# LM-008.net
KiCad netlist of a schematic drawn in Altium Designer
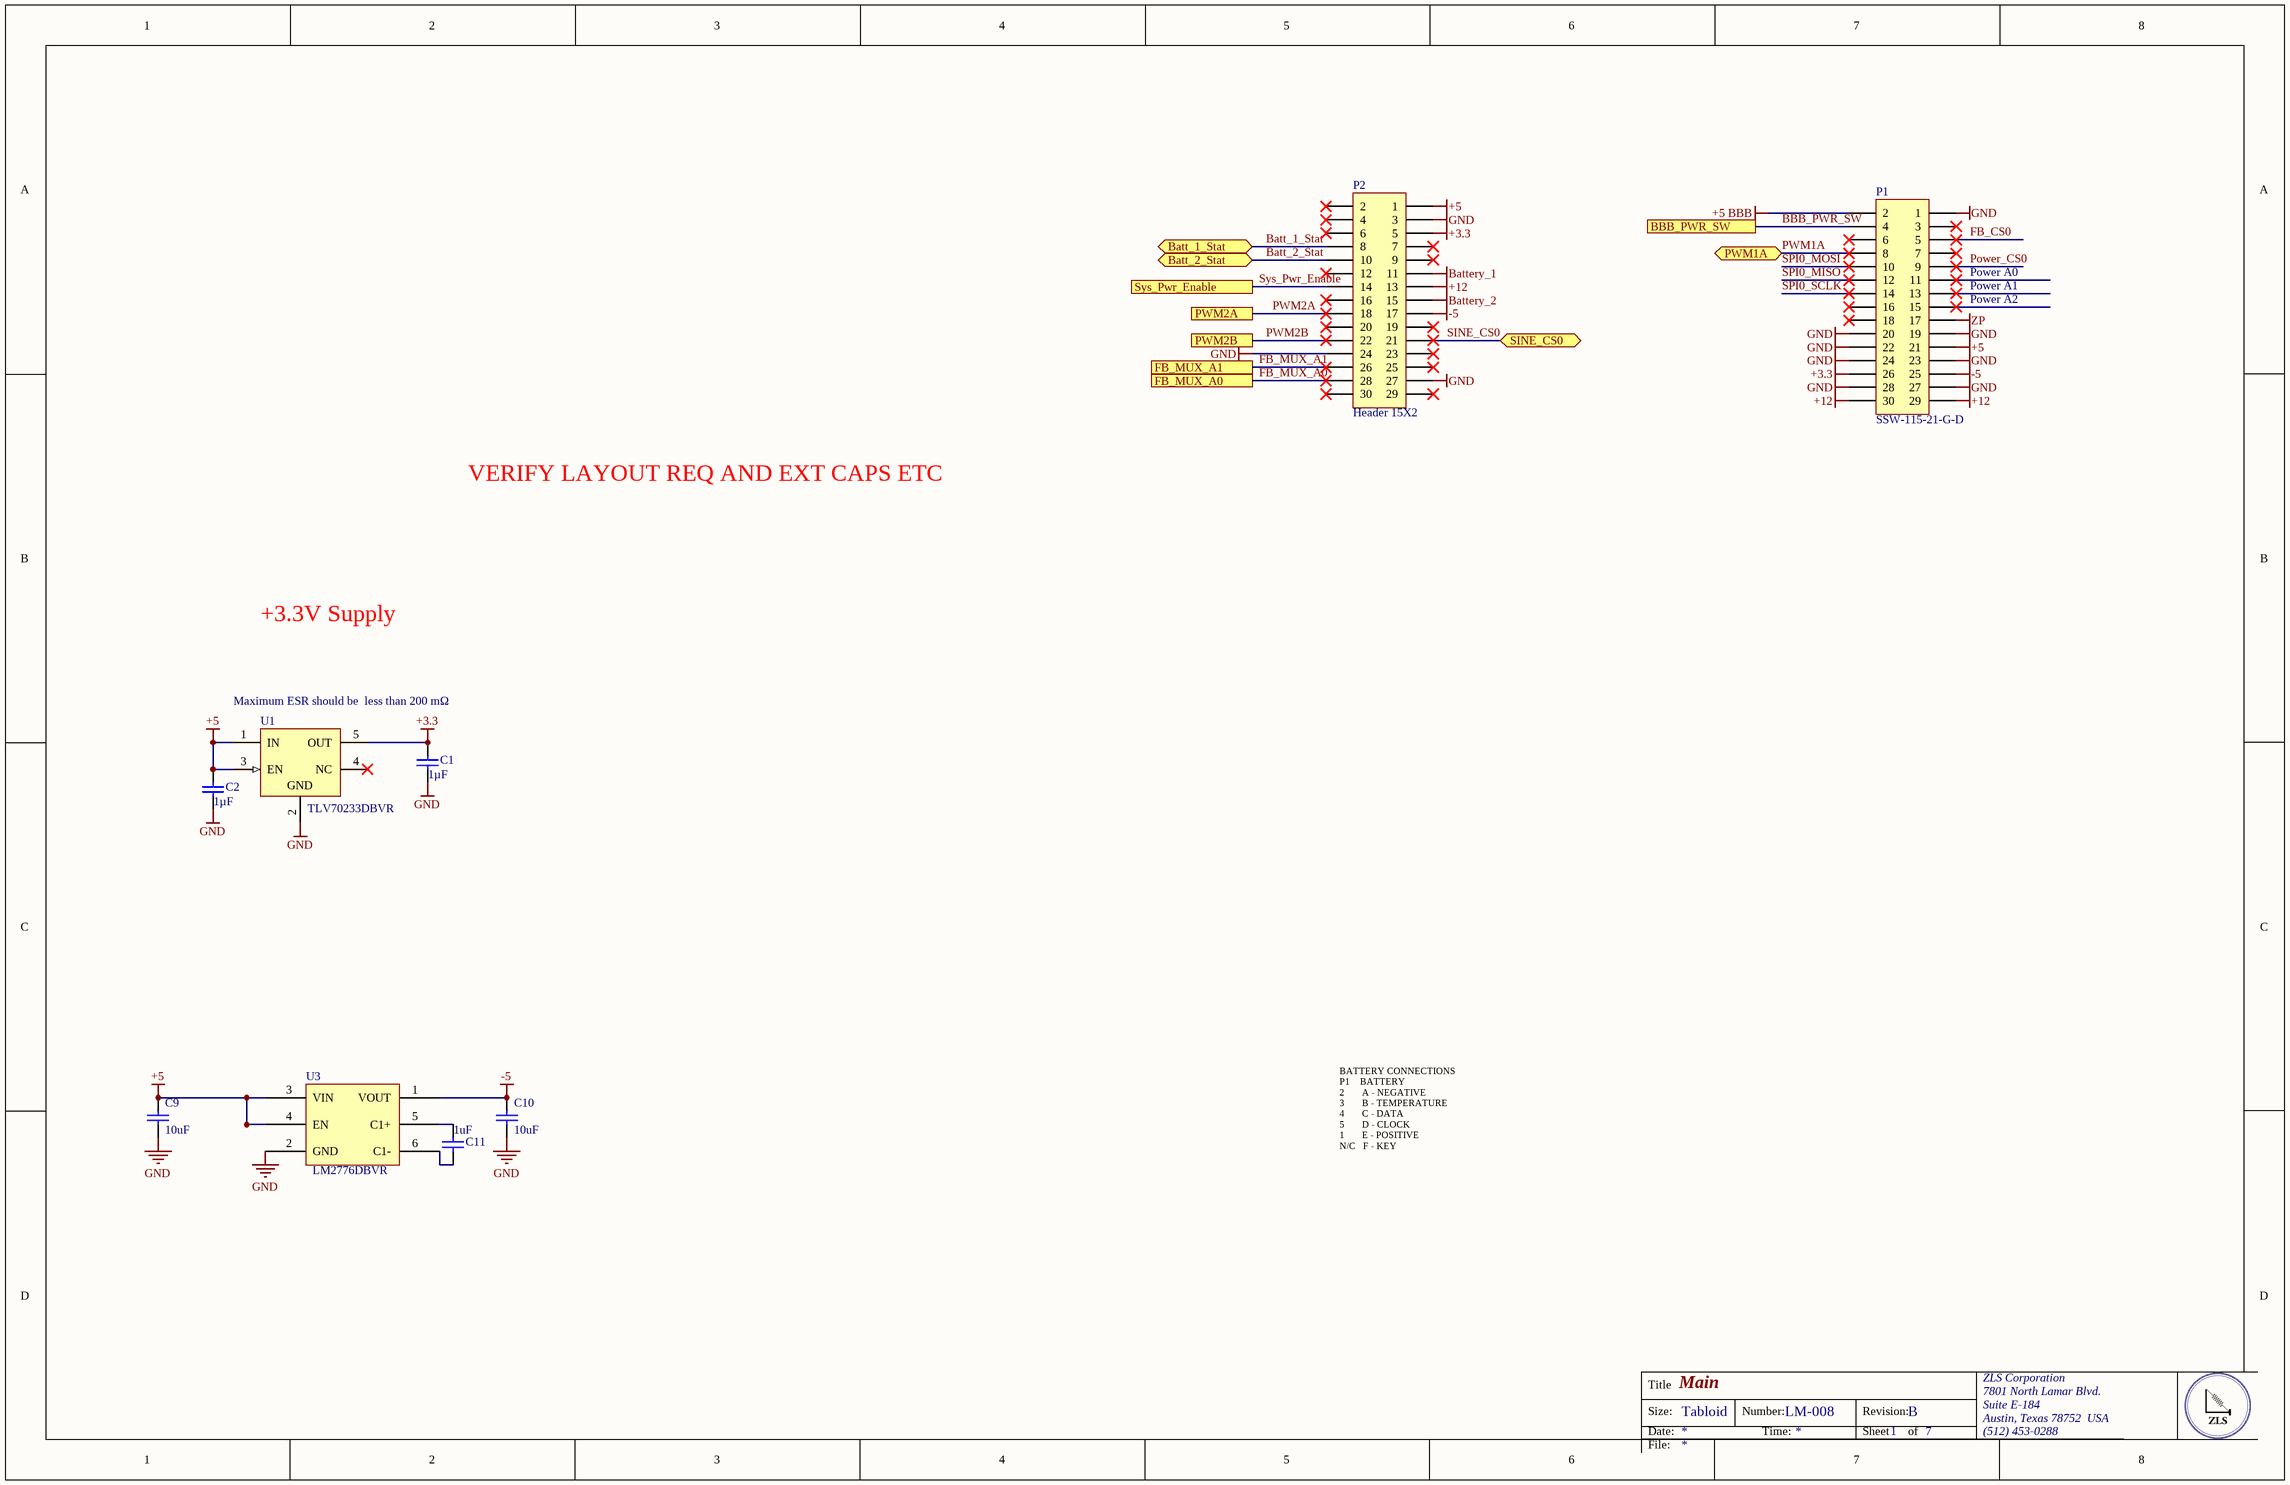
[diagram p0: LM-008.SchDoc]

(export (version "E")
  (design (tool "Eeschema 10.0.6"))
  (components
    (comp (ref "C1")
      (value "CAP CER 1UF 50V X7R 1210")
      (footprint "CAPC1206(3216)130_N")
      (fields
        (field (name "MANUFACTURER") "Murata Electronics North America")
        (field (name "MANUFACTURER PART NUMBER") "GRM32RR71H105KA01L")
        (field (name "CAPACITANCE") "1µF")
        (field (name "TOLERANCE") "±10%")
      )
      (libsource (lib "Altium Content Vault") (part "CMP-1037-04913-1"))
    )
    (comp (ref "C2")
      (value "CAP CER 1UF 50V X7R 1210")
      (footprint "CAPC1206(3216)130_N")
      (fields
        (field (name "MANUFACTURER") "Murata Electronics North America")
        (field (name "MANUFACTURER PART NUMBER") "GRM32RR71H105KA01L")
        (field (name "CAPACITANCE") "1µF")
        (field (name "TOLERANCE") "±10%")
      )
      (libsource (lib "Altium Content Vault") (part "CMP-1037-04913-1"))
    )
    (comp (ref "C9")
      (value "10uF")
      (footprint "CAPC0805(2012)145_N")
      (description "CAP CER 10UF 16V X6S 0805")
      (fields
        (field (name "MANUFACTURER") "TDK Corporation")
        (field (name "MANUFACTURER PART NUMBER") "C2012X6S1C106K085AC")
      )
      (libsource (lib "Altium Content Vault") (part "CMP-1036-04795-1"))
    )
    (comp (ref "C10")
      (value "10uF")
      (footprint "CAPC0805(2012)145_N")
      (description "CAP CER 10UF 16V X6S 0805")
      (fields
        (field (name "MANUFACTURER") "TDK Corporation")
        (field (name "MANUFACTURER PART NUMBER") "C2012X6S1C106K085AC")
      )
      (libsource (lib "Altium Content Vault") (part "CMP-1036-04795-1"))
    )
    (comp (ref "C11")
      (value "1uF")
      (footprint "CAPC0805(2012)145_N")
      (description "CAP CER 1UF 25V X7R 0805")
      (fields
        (field (name "MANUFACTURER") "Yageo")
        (field (name "MANUFACTURER PART NUMBER") "CC0805KKX7R6BB105")
      )
      (libsource (lib "Altium Content Vault") (part "CMP-1036-04795-1"))
    )
    (comp (ref "P1")
      (value "SSW-115-21-G-D")
      (footprint "HDR2X15")
      (description "Header, 15-Pin, Dual row")
      (fields (field (name "MANUFACTURER") "Samtec Inc."))
      (libsource (lib "Miscellaneous Connectors") (part "Header 15X2"))
    )
    (comp (ref "P2")
      (value "Header 15X2")
      (footprint "HDR2X15")
      (description "Header, 15-Pin, Dual row")
      (fields (field (name "PUBLISHER") "Altium Limited"))
      (libsource (lib "Miscellaneous Connectors") (part "Header 15X2"))
    )
    (comp (ref "U1")
      (value "TLV70233DBVR")
      (footprint "DBV0005A_N")
      (fields (field (name "MANUFACTURER") "Texas Instruments"))
      (libsource (lib "Altium Content Vault") (part "TI-TXX7XXXX-5"))
    )
    (comp (ref "U3")
      (value "LM2776DBVR")
      (footprint "LM2776DBVR")
      (description "IC REG SWTCHD CAP INV 6SOT23")
      (fields (field (name "MANUFACTURER") "Texas Instruments"))
      (libsource (lib "ZLS_Schematic_lib") (part "LM2776DBVR"))
    )
  )
  (nets
    (net (code "1") (name "+3.3") (class "Default")
      (node (ref "C1") (pin "2") (pinfunction "2_2") (pintype "passive"))
      (node (ref "P1") (pin "26") (pinfunction "26_26") (pintype "passive"))
      (node (ref "P2") (pin "5") (pinfunction "5_5") (pintype "passive"))
      (node (ref "U1") (pin "5") (pinfunction "OUT_5") (pintype "power_in"))
    )
    (net (code "2") (name "+5") (class "Default")
      (node (ref "C2") (pin "2") (pinfunction "2_2") (pintype "passive"))
      (node (ref "C9") (pin "1") (pinfunction "1_1") (pintype "passive"))
      (node (ref "P1") (pin "21") (pinfunction "21_21") (pintype "passive"))
      (node (ref "P2") (pin "1") (pinfunction "1_1") (pintype "passive"))
      (node (ref "U1") (pin "1") (pinfunction "IN_1") (pintype "power_in"))
      (node (ref "U1") (pin "3") (pinfunction "EN_3") (pintype "input"))
      (node (ref "U3") (pin "3") (pinfunction "VIN_3") (pintype "passive"))
      (node (ref "U3") (pin "4") (pinfunction "EN_4") (pintype "passive"))
    )
    (net (code "3") (name "+5 BBB") (class "Default")
      (node (ref "P1") (pin "2") (pinfunction "2_2") (pintype "passive"))
    )
    (net (code "4") (name "+12") (class "Default")
      (node (ref "P1") (pin "29") (pinfunction "29_29") (pintype "passive"))
      (node (ref "P1") (pin "30") (pinfunction "30_30") (pintype "passive"))
      (node (ref "P2") (pin "13") (pinfunction "13_13") (pintype "passive"))
    )
    (net (code "5") (name "-5") (class "Default")
      (node (ref "C10") (pin "1") (pinfunction "1_1") (pintype "passive"))
      (node (ref "P1") (pin "25") (pinfunction "25_25") (pintype "passive"))
      (node (ref "P2") (pin "17") (pinfunction "17_17") (pintype "passive"))
      (node (ref "U3") (pin "1") (pinfunction "VOUT_1") (pintype "passive"))
    )
    (net (code "6") (name "/BBB_PWR_SW") (class "Default")
      (node (ref "P1") (pin "4") (pinfunction "4_4") (pintype "passive"))
    )
    (net (code "7") (name "/Batt_1_Stat") (class "Default")
      (node (ref "P2") (pin "8") (pinfunction "8_8") (pintype "passive"))
    )
    (net (code "8") (name "/Batt_2_Stat") (class "Default")
      (node (ref "P2") (pin "10") (pinfunction "10_10") (pintype "passive"))
    )
    (net (code "9") (name "/FB_CS0") (class "Default")
      (node (ref "P1") (pin "5") (pinfunction "5_5") (pintype "passive+no_connect"))
    )
    (net (code "10") (name "/FB_MUX_A0") (class "Default")
      (node (ref "P2") (pin "28") (pinfunction "28_28") (pintype "passive+no_connect"))
    )
    (net (code "11") (name "/FB_MUX_A1") (class "Default")
      (node (ref "P2") (pin "26") (pinfunction "26_26") (pintype "passive+no_connect"))
    )
    (net (code "12") (name "/PWM1A") (class "Default")
      (node (ref "P1") (pin "8") (pinfunction "8_8") (pintype "passive+no_connect"))
    )
    (net (code "13") (name "/PWM2A") (class "Default")
      (node (ref "P2") (pin "18") (pinfunction "18_18") (pintype "passive+no_connect"))
    )
    (net (code "14") (name "/PWM2B") (class "Default")
      (node (ref "P2") (pin "22") (pinfunction "22_22") (pintype "passive+no_connect"))
    )
    (net (code "15") (name "/Power_CS0") (class "Default")
      (node (ref "P1") (pin "9") (pinfunction "9_9") (pintype "passive+no_connect"))
    )
    (net (code "16") (name "/SINE_CS0") (class "Default")
      (node (ref "P2") (pin "21") (pinfunction "21_21") (pintype "passive+no_connect"))
    )
    (net (code "17") (name "/SPI0_MISO") (class "Default")
      (node (ref "P1") (pin "12") (pinfunction "12_12") (pintype "passive+no_connect"))
    )
    (net (code "18") (name "/SPI0_MOSI") (class "Default")
      (node (ref "P1") (pin "10") (pinfunction "10_10") (pintype "passive+no_connect"))
    )
    (net (code "19") (name "/SPI0_SCLK") (class "Default")
      (node (ref "P1") (pin "14") (pinfunction "14_14") (pintype "passive+no_connect"))
    )
    (net (code "20") (name "/Sys_Pwr_Enable") (class "Default")
      (node (ref "P2") (pin "14") (pinfunction "14_14") (pintype "passive"))
    )
    (net (code "21") (name "Battery_1") (class "Default")
      (node (ref "P2") (pin "11") (pinfunction "11_11") (pintype "passive"))
    )
    (net (code "22") (name "Battery_2") (class "Default")
      (node (ref "P2") (pin "15") (pinfunction "15_15") (pintype "passive"))
    )
    (net (code "23") (name "GND") (class "Default")
      (node (ref "C1") (pin "1") (pinfunction "1_1") (pintype "passive"))
      (node (ref "C10") (pin "2") (pinfunction "2_2") (pintype "passive"))
      (node (ref "C2") (pin "1") (pinfunction "1_1") (pintype "passive"))
      (node (ref "C9") (pin "2") (pinfunction "2_2") (pintype "passive"))
      (node (ref "P1") (pin "1") (pinfunction "1_1") (pintype "passive"))
      (node (ref "P1") (pin "19") (pinfunction "19_19") (pintype "passive"))
      (node (ref "P1") (pin "20") (pinfunction "20_20") (pintype "passive"))
      (node (ref "P1") (pin "22") (pinfunction "22_22") (pintype "passive"))
      (node (ref "P1") (pin "23") (pinfunction "23_23") (pintype "passive"))
      (node (ref "P1") (pin "24") (pinfunction "24_24") (pintype "passive"))
      (node (ref "P1") (pin "27") (pinfunction "27_27") (pintype "passive"))
      (node (ref "P1") (pin "28") (pinfunction "28_28") (pintype "passive"))
      (node (ref "P2") (pin "24") (pinfunction "24_24") (pintype "passive"))
      (node (ref "P2") (pin "27") (pinfunction "27_27") (pintype "passive"))
      (node (ref "P2") (pin "3") (pinfunction "3_3") (pintype "passive"))
      (node (ref "U1") (pin "2") (pinfunction "GND_2") (pintype "power_in"))
      (node (ref "U3") (pin "2") (pinfunction "GND_2") (pintype "passive"))
    )
    (net (code "24") (name "Net-(U3-C1+)") (class "Default")
      (node (ref "C11") (pin "1") (pinfunction "1_1") (pintype "passive"))
      (node (ref "U3") (pin "5") (pinfunction "C1+_5") (pintype "passive"))
    )
    (net (code "25") (name "Net-(U3-C1-)") (class "Default")
      (node (ref "C11") (pin "2") (pinfunction "2_2") (pintype "passive"))
      (node (ref "U3") (pin "6") (pinfunction "C1-_6") (pintype "passive"))
    )
    (net (code "26") (name "ZP") (class "Default")
      (node (ref "P1") (pin "17") (pinfunction "17_17") (pintype "passive"))
    )
    (net (code "27") (name "unconnected-(P1-Pad3)") (class "Default")
      (node (ref "P1") (pin "3") (pinfunction "3_3") (pintype "passive+no_connect"))
    )
    (net (code "28") (name "unconnected-(P1-Pad6)") (class "Default")
      (node (ref "P1") (pin "6") (pinfunction "6_6") (pintype "passive+no_connect"))
    )
    (net (code "29") (name "unconnected-(P1-Pad7)") (class "Default")
      (node (ref "P1") (pin "7") (pinfunction "7_7") (pintype "passive+no_connect"))
    )
    (net (code "30") (name "unconnected-(P1-Pad11)") (class "Default")
      (node (ref "P1") (pin "11") (pinfunction "11_11") (pintype "passive+no_connect"))
    )
    (net (code "31") (name "unconnected-(P1-Pad13)") (class "Default")
      (node (ref "P1") (pin "13") (pinfunction "13_13") (pintype "passive+no_connect"))
    )
    (net (code "32") (name "unconnected-(P1-Pad15)") (class "Default")
      (node (ref "P1") (pin "15") (pinfunction "15_15") (pintype "passive+no_connect"))
    )
    (net (code "33") (name "unconnected-(P1-Pad16)") (class "Default")
      (node (ref "P1") (pin "16") (pinfunction "16_16") (pintype "passive+no_connect"))
    )
    (net (code "34") (name "unconnected-(P1-Pad18)") (class "Default")
      (node (ref "P1") (pin "18") (pinfunction "18_18") (pintype "passive+no_connect"))
    )
    (net (code "35") (name "unconnected-(P2-Pad2)") (class "Default")
      (node (ref "P2") (pin "2") (pinfunction "2_2") (pintype "passive+no_connect"))
    )
    (net (code "36") (name "unconnected-(P2-Pad4)") (class "Default")
      (node (ref "P2") (pin "4") (pinfunction "4_4") (pintype "passive+no_connect"))
    )
    (net (code "37") (name "unconnected-(P2-Pad6)") (class "Default")
      (node (ref "P2") (pin "6") (pinfunction "6_6") (pintype "passive+no_connect"))
    )
    (net (code "38") (name "unconnected-(P2-Pad7)") (class "Default")
      (node (ref "P2") (pin "7") (pinfunction "7_7") (pintype "passive+no_connect"))
    )
    (net (code "39") (name "unconnected-(P2-Pad9)") (class "Default")
      (node (ref "P2") (pin "9") (pinfunction "9_9") (pintype "passive+no_connect"))
    )
    (net (code "40") (name "unconnected-(P2-Pad12)") (class "Default")
      (node (ref "P2") (pin "12") (pinfunction "12_12") (pintype "passive+no_connect"))
    )
    (net (code "41") (name "unconnected-(P2-Pad16)") (class "Default")
      (node (ref "P2") (pin "16") (pinfunction "16_16") (pintype "passive+no_connect"))
    )
    (net (code "42") (name "unconnected-(P2-Pad19)") (class "Default")
      (node (ref "P2") (pin "19") (pinfunction "19_19") (pintype "passive+no_connect"))
    )
    (net (code "43") (name "unconnected-(P2-Pad20)") (class "Default")
      (node (ref "P2") (pin "20") (pinfunction "20_20") (pintype "passive+no_connect"))
    )
    (net (code "44") (name "unconnected-(P2-Pad23)") (class "Default")
      (node (ref "P2") (pin "23") (pinfunction "23_23") (pintype "passive+no_connect"))
    )
    (net (code "45") (name "unconnected-(P2-Pad25)") (class "Default")
      (node (ref "P2") (pin "25") (pinfunction "25_25") (pintype "passive+no_connect"))
    )
    (net (code "46") (name "unconnected-(P2-Pad29)") (class "Default")
      (node (ref "P2") (pin "29") (pinfunction "29_29") (pintype "passive+no_connect"))
    )
    (net (code "47") (name "unconnected-(P2-Pad30)") (class "Default")
      (node (ref "P2") (pin "30") (pinfunction "30_30") (pintype "passive+no_connect"))
    )
    (net (code "48") (name "unconnected-(U1-NC-Pad4)") (class "Default")
      (node (ref "U1") (pin "4") (pinfunction "NC_4") (pintype "passive+no_connect"))
    )
  )
)
